# 05_IO_CONN.net
KiCad netlist of a schematic drawn in Altium Designer
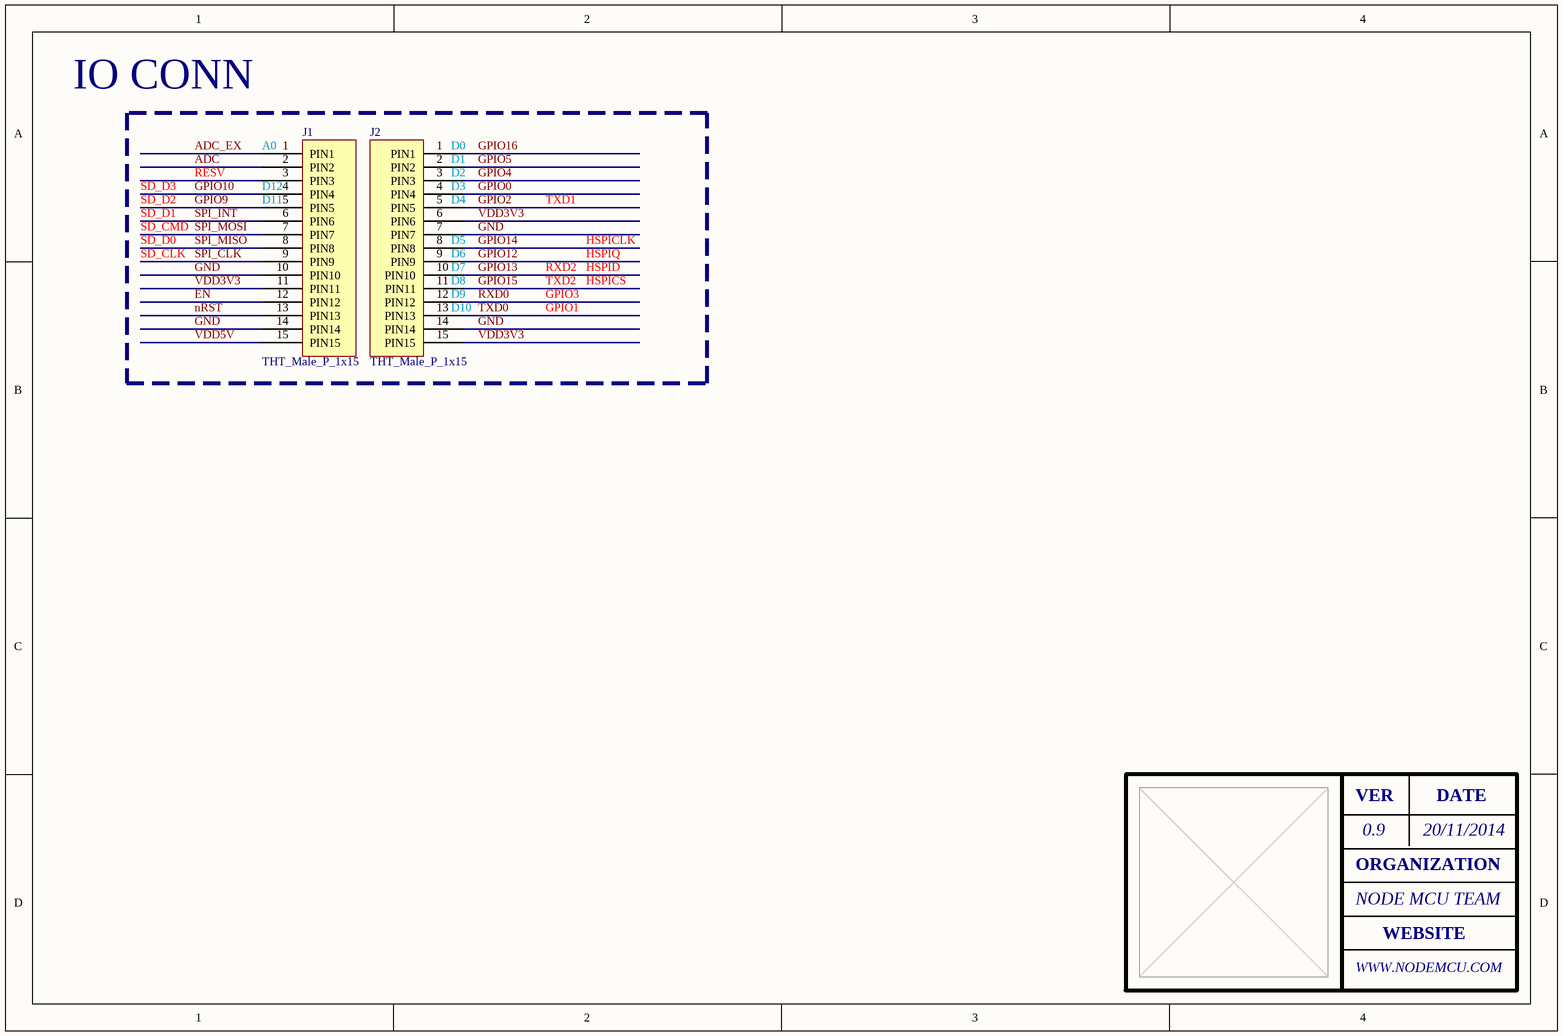
[diagram p0: 05_IO_CONN.SchDoc]

(export (version "E")
  (design (tool "Eeschema 10.0.6"))
  (components
    (comp (ref "J1")
      (value "THT_Male_P_1x15")
      (footprint "THT_Male_P_1x15-2.54mm")
      (description "THT Male pin header strip 1x15")
      (libsource (lib "Vowstar_Connector") (part "THT_Male_P_1x15"))
    )
    (comp (ref "J2")
      (value "THT_Male_P_1x15")
      (footprint "THT_Male_P_1x15-2.54mm")
      (description "THT Male pin header strip 1x15")
      (libsource (lib "") (part "THT_Male_P_1x15_1"))
    )
  )
  (nets
    (net (code "1") (name "/ADC") (class "Default")
      (node (ref "J1") (pin "2") (pinfunction "PIN2_2") (pintype "passive"))
    )
    (net (code "2") (name "/ADC_EX") (class "Default")
      (node (ref "J1") (pin "1") (pinfunction "PIN1_1") (pintype "passive"))
    )
    (net (code "3") (name "/EN") (class "Default")
      (node (ref "J1") (pin "12") (pinfunction "PIN12_12") (pintype "passive"))
    )
    (net (code "4") (name "/GND") (class "Default")
      (node (ref "J1") (pin "10") (pinfunction "PIN10_10") (pintype "passive"))
      (node (ref "J1") (pin "14") (pinfunction "PIN14_14") (pintype "passive"))
      (node (ref "J2") (pin "14") (pinfunction "PIN14_14") (pintype "passive"))
      (node (ref "J2") (pin "7") (pinfunction "PIN7_7") (pintype "passive"))
    )
    (net (code "5") (name "/GPIO0") (class "Default")
      (node (ref "J2") (pin "4") (pinfunction "PIN4_4") (pintype "passive"))
    )
    (net (code "6") (name "/GPIO2") (class "Default")
      (node (ref "J2") (pin "5") (pinfunction "PIN5_5") (pintype "passive"))
    )
    (net (code "7") (name "/GPIO4") (class "Default")
      (node (ref "J2") (pin "3") (pinfunction "PIN3_3") (pintype "passive"))
    )
    (net (code "8") (name "/GPIO5") (class "Default")
      (node (ref "J2") (pin "2") (pinfunction "PIN2_2") (pintype "passive"))
    )
    (net (code "9") (name "/GPIO9") (class "Default")
      (node (ref "J1") (pin "5") (pinfunction "PIN5_5") (pintype "passive"))
    )
    (net (code "10") (name "/GPIO10") (class "Default")
      (node (ref "J1") (pin "4") (pinfunction "PIN4_4") (pintype "passive"))
    )
    (net (code "11") (name "/GPIO12") (class "Default")
      (node (ref "J2") (pin "9") (pinfunction "PIN9_9") (pintype "passive"))
    )
    (net (code "12") (name "/GPIO13") (class "Default")
      (node (ref "J2") (pin "10") (pinfunction "PIN10_10") (pintype "passive"))
    )
    (net (code "13") (name "/GPIO14") (class "Default")
      (node (ref "J2") (pin "8") (pinfunction "PIN8_8") (pintype "passive"))
    )
    (net (code "14") (name "/GPIO15") (class "Default")
      (node (ref "J2") (pin "11") (pinfunction "PIN11_11") (pintype "passive"))
    )
    (net (code "15") (name "/GPIO16") (class "Default")
      (node (ref "J2") (pin "1") (pinfunction "PIN1_1") (pintype "passive"))
    )
    (net (code "16") (name "/RXD0") (class "Default")
      (node (ref "J2") (pin "12") (pinfunction "PIN12_12") (pintype "passive"))
    )
    (net (code "17") (name "/SPI_CLK") (class "Default")
      (node (ref "J1") (pin "9") (pinfunction "PIN9_9") (pintype "passive"))
    )
    (net (code "18") (name "/SPI_INT") (class "Default")
      (node (ref "J1") (pin "6") (pinfunction "PIN6_6") (pintype "passive"))
    )
    (net (code "19") (name "/SPI_MISO") (class "Default")
      (node (ref "J1") (pin "8") (pinfunction "PIN8_8") (pintype "passive"))
    )
    (net (code "20") (name "/SPI_MOSI") (class "Default")
      (node (ref "J1") (pin "7") (pinfunction "PIN7_7") (pintype "passive"))
    )
    (net (code "21") (name "/TXD0") (class "Default")
      (node (ref "J2") (pin "13") (pinfunction "PIN13_13") (pintype "passive"))
    )
    (net (code "22") (name "/VDD3V3") (class "Default")
      (node (ref "J1") (pin "11") (pinfunction "PIN11_11") (pintype "passive"))
      (node (ref "J2") (pin "15") (pinfunction "PIN15_15") (pintype "passive"))
      (node (ref "J2") (pin "6") (pinfunction "PIN6_6") (pintype "passive"))
    )
    (net (code "23") (name "/VDD5V") (class "Default")
      (node (ref "J1") (pin "15") (pinfunction "PIN15_15") (pintype "passive"))
    )
    (net (code "24") (name "/nRST") (class "Default")
      (node (ref "J1") (pin "13") (pinfunction "PIN13_13") (pintype "passive"))
    )
    (net (code "25") (name "unconnected-(J1-PIN3-Pad3)") (class "Default")
      (node (ref "J1") (pin "3") (pinfunction "PIN3_3") (pintype "passive"))
    )
  )
)
